# Communication.net
KiCad netlist of a schematic drawn in Altium Designer
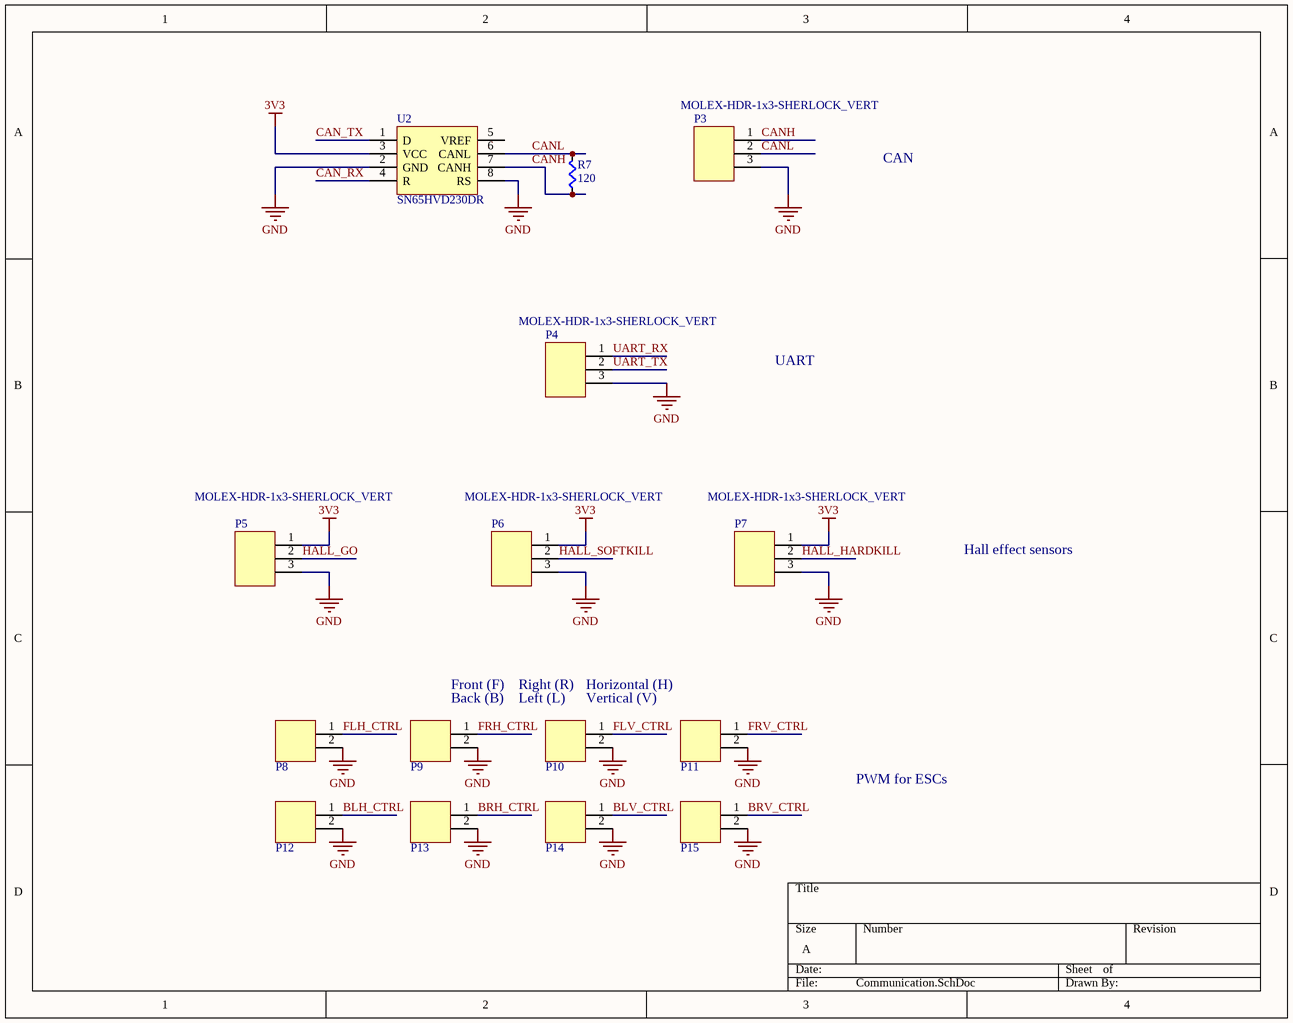
[diagram p0: Communication.SchDoc]

(export (version "E")
  (design (tool "Eeschema 10.0.6"))
  (components
    (comp (ref "P3")
      (value "MOLEX-HDR-1x3-SHERLOCK_VERT")
      (footprint "MOLEX-HDR-1X3-SHERLOCK-VERT")
      (libsource (lib "SubjuGator8") (part "MOLEX-HDR-1x3-SHERLOCK_VERT"))
    )
    (comp (ref "P4")
      (value "MOLEX-HDR-1x3-SHERLOCK_VERT")
      (footprint "MOLEX-HDR-1X3-SHERLOCK-VERT")
      (libsource (lib "SubjuGator8") (part "MOLEX-HDR-1x3-SHERLOCK_VERT"))
    )
    (comp (ref "P5")
      (value "MOLEX-HDR-1x3-SHERLOCK_VERT")
      (footprint "MOLEX-HDR-1X3-SHERLOCK-VERT")
      (libsource (lib "SubjuGator8") (part "MOLEX-HDR-1x3-SHERLOCK_VERT"))
    )
    (comp (ref "P6")
      (value "MOLEX-HDR-1x3-SHERLOCK_VERT")
      (footprint "MOLEX-HDR-1X3-SHERLOCK-VERT")
      (libsource (lib "SubjuGator8") (part "MOLEX-HDR-1x3-SHERLOCK_VERT"))
    )
    (comp (ref "P7")
      (value "MOLEX-HDR-1x3-SHERLOCK_VERT")
      (footprint "MOLEX-HDR-1X3-SHERLOCK-VERT")
      (libsource (lib "SubjuGator8") (part "MOLEX-HDR-1x3-SHERLOCK_VERT"))
    )
    (comp (ref "P8")
      (value "2-pin Vert Sherlock")
      (footprint "MOLEX-HDR-1X2-SHERLOCK-VERT")
      (libsource (lib "SubjuGator8") (part "MOLEX-HDR-1x2-SHERLOCK_VERT"))
    )
    (comp (ref "P9")
      (value "2-pin Vert Sherlock")
      (footprint "MOLEX-HDR-1X2-SHERLOCK-VERT")
      (libsource (lib "SubjuGator8") (part "MOLEX-HDR-1x2-SHERLOCK_VERT"))
    )
    (comp (ref "P10")
      (value "2-pin Vert Sherlock")
      (footprint "MOLEX-HDR-1X2-SHERLOCK-VERT")
      (libsource (lib "SubjuGator8") (part "MOLEX-HDR-1x2-SHERLOCK_VERT"))
    )
    (comp (ref "P11")
      (value "2-pin Vert Sherlock")
      (footprint "MOLEX-HDR-1X2-SHERLOCK-VERT")
      (libsource (lib "SubjuGator8") (part "MOLEX-HDR-1x2-SHERLOCK_VERT"))
    )
    (comp (ref "P12")
      (value "2-pin Vert Sherlock")
      (footprint "MOLEX-HDR-1X2-SHERLOCK-VERT")
      (libsource (lib "SubjuGator8") (part "MOLEX-HDR-1x2-SHERLOCK_VERT"))
    )
    (comp (ref "P13")
      (value "2-pin Vert Sherlock")
      (footprint "MOLEX-HDR-1X2-SHERLOCK-VERT")
      (libsource (lib "SubjuGator8") (part "MOLEX-HDR-1x2-SHERLOCK_VERT"))
    )
    (comp (ref "P14")
      (value "2-pin Vert Sherlock")
      (footprint "MOLEX-HDR-1X2-SHERLOCK-VERT")
      (libsource (lib "SubjuGator8") (part "MOLEX-HDR-1x2-SHERLOCK_VERT"))
    )
    (comp (ref "P15")
      (value "2-pin Vert Sherlock")
      (footprint "MOLEX-HDR-1X2-SHERLOCK-VERT")
      (libsource (lib "SubjuGator8") (part "MOLEX-HDR-1x2-SHERLOCK_VERT"))
    )
    (comp (ref "R7")
      (value "120")
      (footprint "RES0603")
      (fields (field (name "Comment") "Res"))
      (libsource (lib "SubjuGator8") (part "Res"))
    )
    (comp (ref "U2")
      (value "SN65HVD230DR")
      (footprint "SOIC-8pin")
      (description "3.3V CAN Bus Transciever")
      (libsource (lib "SubjuGator8") (part "SN65HVD230DR"))
    )
  )
  (nets
    (net (code "1") (name "/BLH_CTRL") (class "Default")
      (node (ref "P12") (pin "1") (pinfunction "1_1") (pintype "passive"))
    )
    (net (code "2") (name "/BLV_CTRL") (class "Default")
      (node (ref "P14") (pin "1") (pinfunction "1_1") (pintype "passive"))
    )
    (net (code "3") (name "/BRH_CTRL") (class "Default")
      (node (ref "P13") (pin "1") (pinfunction "1_1") (pintype "passive"))
    )
    (net (code "4") (name "/BRV_CTRL") (class "Default")
      (node (ref "P15") (pin "1") (pinfunction "1_1") (pintype "passive"))
    )
    (net (code "5") (name "/CANH") (class "Default")
      (node (ref "P3") (pin "1") (pinfunction "1_1") (pintype "passive"))
      (node (ref "R7") (pin "2") (pinfunction "B_2") (pintype "passive"))
      (node (ref "U2") (pin "7") (pinfunction "CANH_7") (pintype "passive"))
    )
    (net (code "6") (name "/CANL") (class "Default")
      (node (ref "P3") (pin "2") (pinfunction "2_2") (pintype "passive"))
      (node (ref "R7") (pin "1") (pinfunction "A_1") (pintype "passive"))
      (node (ref "U2") (pin "6") (pinfunction "CANL_6") (pintype "passive"))
    )
    (net (code "7") (name "/CAN_RX") (class "Default")
      (node (ref "U2") (pin "4") (pinfunction "R_4") (pintype "passive"))
    )
    (net (code "8") (name "/CAN_TX") (class "Default")
      (node (ref "U2") (pin "1") (pinfunction "D_1") (pintype "passive"))
    )
    (net (code "9") (name "/FLH_CTRL") (class "Default")
      (node (ref "P8") (pin "1") (pinfunction "1_1") (pintype "passive"))
    )
    (net (code "10") (name "/FLV_CTRL") (class "Default")
      (node (ref "P10") (pin "1") (pinfunction "1_1") (pintype "passive"))
    )
    (net (code "11") (name "/FRH_CTRL") (class "Default")
      (node (ref "P9") (pin "1") (pinfunction "1_1") (pintype "passive"))
    )
    (net (code "12") (name "/FRV_CTRL") (class "Default")
      (node (ref "P11") (pin "1") (pinfunction "1_1") (pintype "passive"))
    )
    (net (code "13") (name "/HALL_GO") (class "Default")
      (node (ref "P5") (pin "2") (pinfunction "2_2") (pintype "passive"))
    )
    (net (code "14") (name "/HALL_HARDKILL") (class "Default")
      (node (ref "P7") (pin "2") (pinfunction "2_2") (pintype "passive"))
    )
    (net (code "15") (name "/HALL_SOFTKILL") (class "Default")
      (node (ref "P6") (pin "2") (pinfunction "2_2") (pintype "passive"))
    )
    (net (code "16") (name "/UART_RX") (class "Default")
      (node (ref "P4") (pin "1") (pinfunction "1_1") (pintype "passive"))
    )
    (net (code "17") (name "/UART_TX") (class "Default")
      (node (ref "P4") (pin "2") (pinfunction "2_2") (pintype "passive"))
    )
    (net (code "18") (name "3V3") (class "Default")
      (node (ref "P5") (pin "1") (pinfunction "1_1") (pintype "passive"))
      (node (ref "P6") (pin "1") (pinfunction "1_1") (pintype "passive"))
      (node (ref "P7") (pin "1") (pinfunction "1_1") (pintype "passive"))
      (node (ref "U2") (pin "3") (pinfunction "VCC_3") (pintype "passive"))
    )
    (net (code "19") (name "GND") (class "Default")
      (node (ref "P10") (pin "2") (pinfunction "2_2") (pintype "passive"))
      (node (ref "P11") (pin "2") (pinfunction "2_2") (pintype "passive"))
      (node (ref "P12") (pin "2") (pinfunction "2_2") (pintype "passive"))
      (node (ref "P13") (pin "2") (pinfunction "2_2") (pintype "passive"))
      (node (ref "P14") (pin "2") (pinfunction "2_2") (pintype "passive"))
      (node (ref "P15") (pin "2") (pinfunction "2_2") (pintype "passive"))
      (node (ref "P3") (pin "3") (pinfunction "3_3") (pintype "passive"))
      (node (ref "P4") (pin "3") (pinfunction "3_3") (pintype "passive"))
      (node (ref "P5") (pin "3") (pinfunction "3_3") (pintype "passive"))
      (node (ref "P6") (pin "3") (pinfunction "3_3") (pintype "passive"))
      (node (ref "P7") (pin "3") (pinfunction "3_3") (pintype "passive"))
      (node (ref "P8") (pin "2") (pinfunction "2_2") (pintype "passive"))
      (node (ref "P9") (pin "2") (pinfunction "2_2") (pintype "passive"))
      (node (ref "U2") (pin "2") (pinfunction "GND_2") (pintype "passive"))
      (node (ref "U2") (pin "8") (pinfunction "RS_8") (pintype "passive"))
    )
    (net (code "20") (name "unconnected-(U2-VREF-Pad5)") (class "Default")
      (node (ref "U2") (pin "5") (pinfunction "VREF_5") (pintype "passive"))
    )
  )
)
